# Pure_VCO.net
KiCad netlist of a schematic drawn in EAGLE
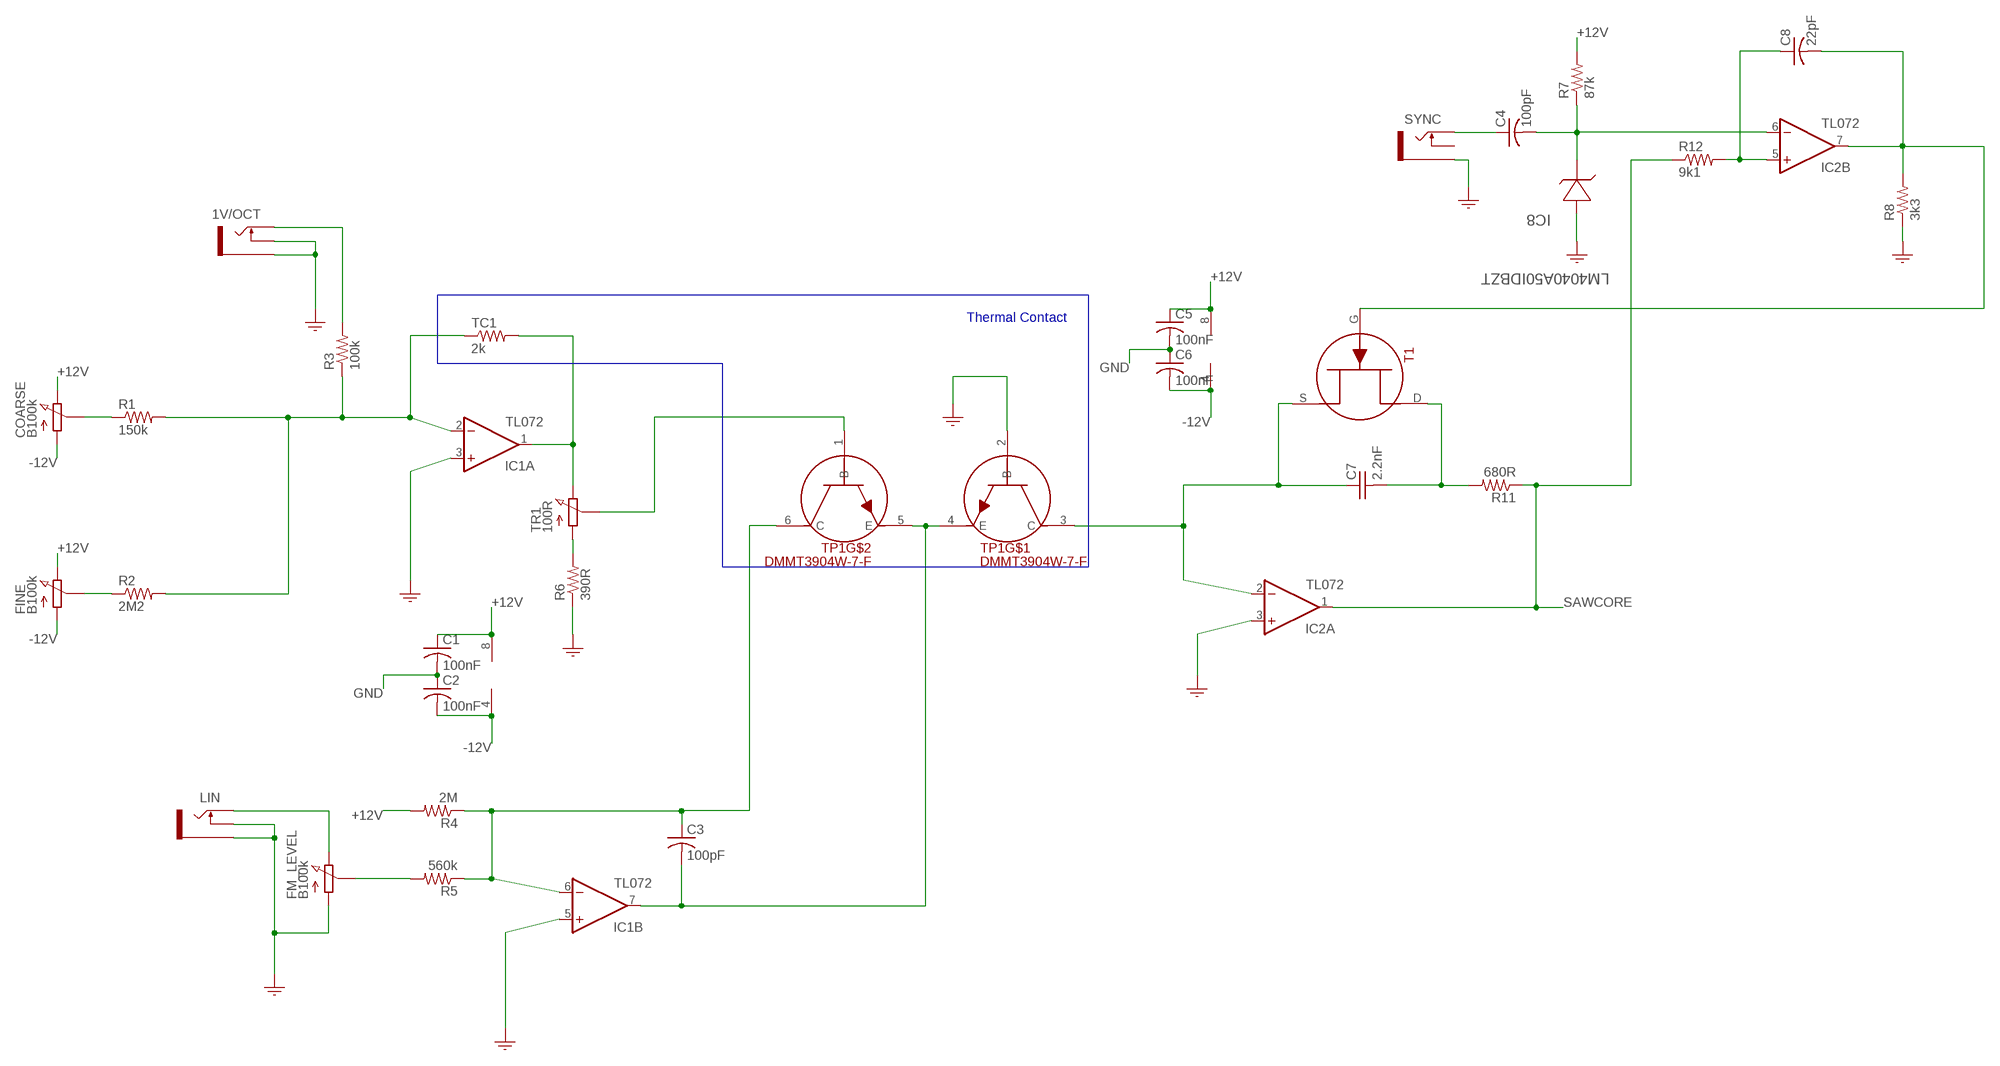
[diagram p0: schematic, sheet 1]
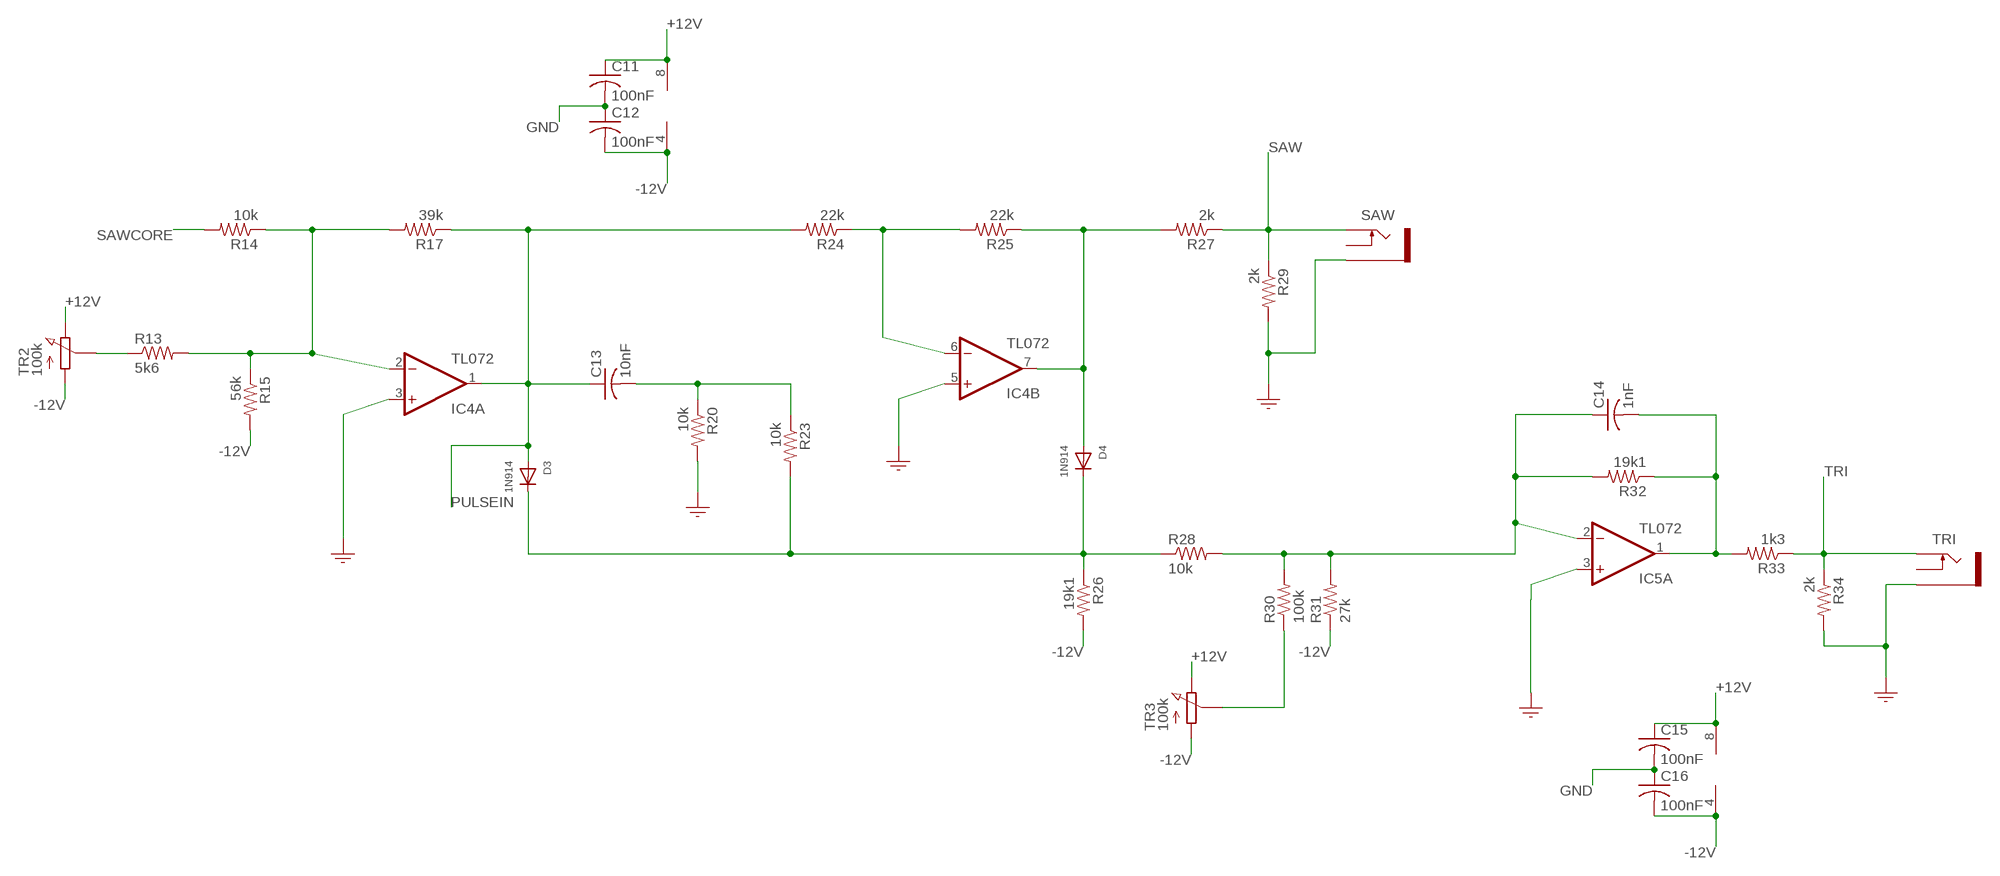
[diagram p1: schematic, sheet 2]
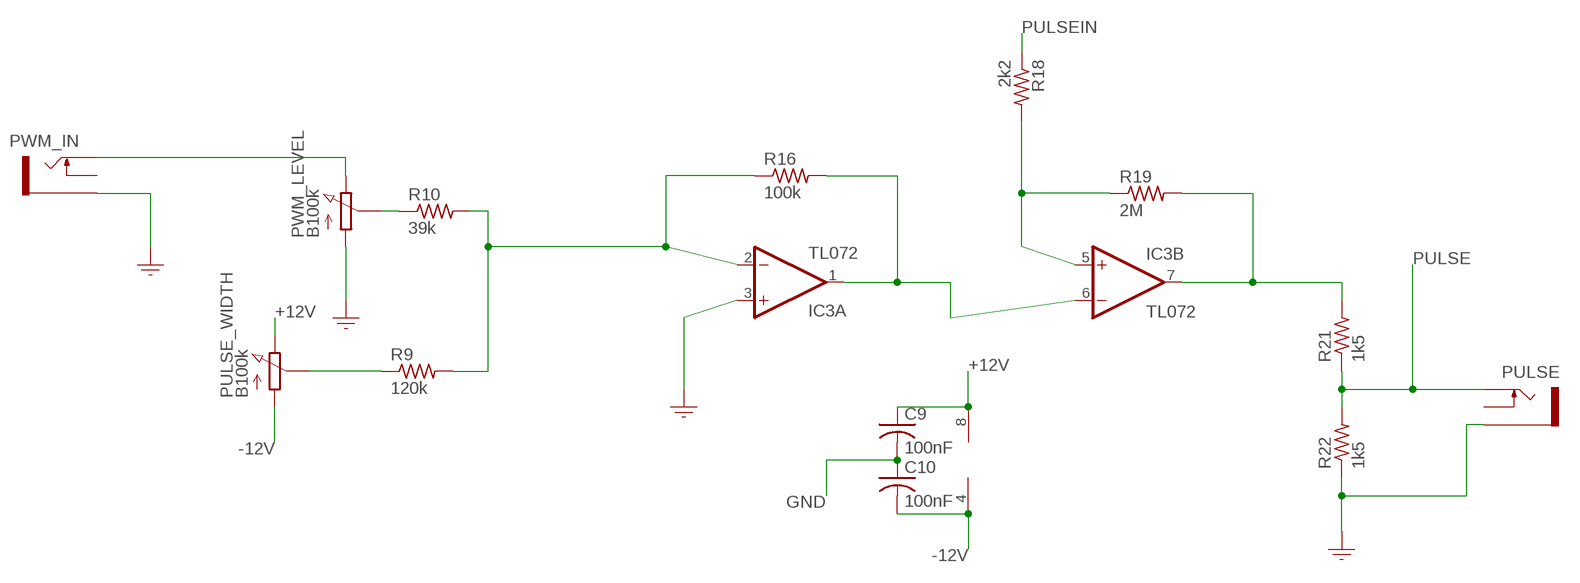
[diagram p2: schematic, sheet 3]
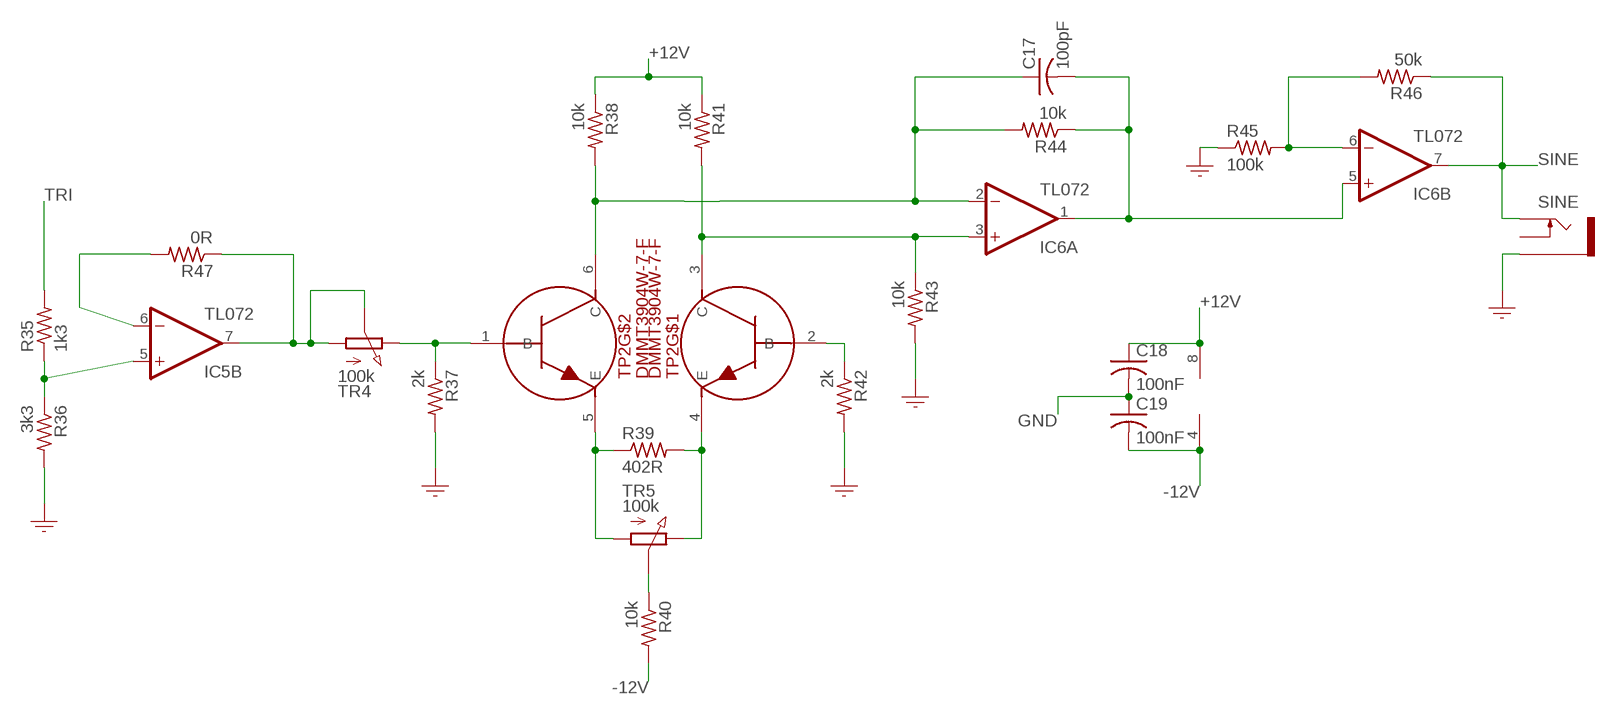
[diagram p3: schematic, sheet 4]
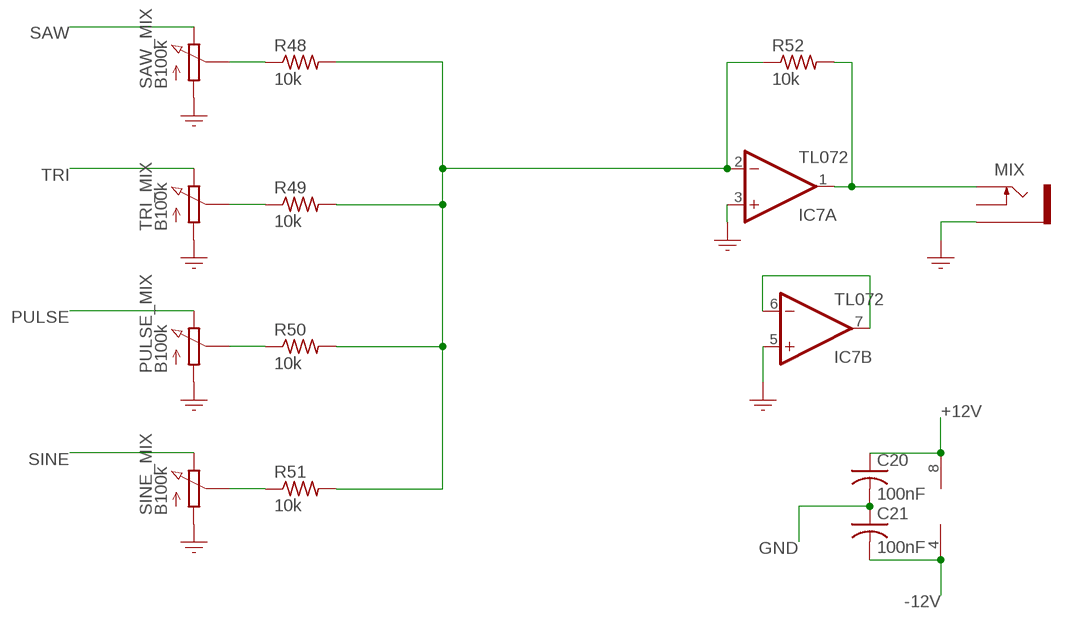
[diagram p4: schematic, sheet 5]
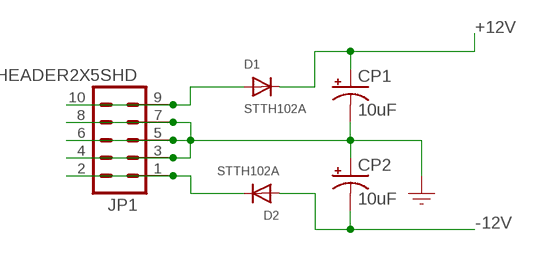
[diagram p5: schematic, sheet 6]

(export (version "E")
  (design (tool "Eeschema 10.0.6"))
  (components
    (comp (ref "C9")
      (value "100nF")
      (footprint "eagle-import:C0805")
      (libsource (lib "eagle-import") (part "CAPACITOR-USC0805"))
    )
    (comp (ref "C10")
      (value "100nF")
      (footprint "eagle-import:C0805")
      (libsource (lib "eagle-import") (part "CAPACITOR-USC0805"))
    )
    (comp (ref "IC3")
      (value "TL072")
      (footprint "eagle-import:SO08")
      (libsource (lib "eagle-import") (part "OPAMP_DUALD"))
    )
    (comp (ref "PULSE")
      (value "PJ301M-12")
      (footprint "eagle-import:PJ301M-12")
      (libsource (lib "eagle-import") (part "SOCKET_MONO_3.5MMPJ301M-12"))
    )
    (comp (ref "PULSE_WIDTH")
      (value "B100k")
      (footprint "eagle-import:POT_9MM_YELLOW_KNOB")
      (libsource (lib "eagle-import") (part "RESISTOR_VARIABLEPOT_9MM_YELLOW_KNOB"))
    )
    (comp (ref "PWM_IN")
      (value "PJ301M-12")
      (footprint "eagle-import:PJ301M-12")
      (libsource (lib "eagle-import") (part "SOCKET_MONO_3.5MMPJ301M-12"))
    )
    (comp (ref "PWM_LEVEL")
      (value "B100k")
      (footprint "eagle-import:POT_9MM_GREEN_KNOB")
      (libsource (lib "eagle-import") (part "RESISTOR_VARIABLEPOT_9MM_GREEN_KNOB"))
    )
    (comp (ref "R9")
      (value "120k")
      (footprint "eagle-import:R0805")
      (libsource (lib "eagle-import") (part "RESISTOR_USR0805"))
    )
    (comp (ref "R10")
      (value "39k")
      (footprint "eagle-import:R0805")
      (libsource (lib "eagle-import") (part "RESISTOR_USR0805"))
    )
    (comp (ref "R16")
      (value "100k")
      (footprint "eagle-import:R0805")
      (libsource (lib "eagle-import") (part "RESISTOR_USR0805"))
    )
    (comp (ref "R18")
      (value "2k2")
      (footprint "eagle-import:R0805")
      (libsource (lib "eagle-import") (part "RESISTOR_USR0805"))
    )
    (comp (ref "R19")
      (value "2M")
      (footprint "eagle-import:R0805")
      (libsource (lib "eagle-import") (part "RESISTOR_USR0805"))
    )
    (comp (ref "R21")
      (value "1k5")
      (footprint "eagle-import:R0805")
      (libsource (lib "eagle-import") (part "RESISTOR_USR0805"))
    )
    (comp (ref "R22")
      (value "1k5")
      (footprint "eagle-import:R0805")
      (libsource (lib "eagle-import") (part "RESISTOR_USR0805"))
    )
    (comp (ref "C11")
      (value "100nF")
      (footprint "eagle-import:C0805")
      (libsource (lib "eagle-import") (part "CAPACITOR-USC0805"))
    )
    (comp (ref "C12")
      (value "100nF")
      (footprint "eagle-import:C0805")
      (libsource (lib "eagle-import") (part "CAPACITOR-USC0805"))
    )
    (comp (ref "C13")
      (value "10nF")
      (footprint "eagle-import:C0805")
      (libsource (lib "eagle-import") (part "CAPACITOR-USC0805"))
    )
    (comp (ref "C14")
      (value "1nF")
      (footprint "eagle-import:C0805")
      (libsource (lib "eagle-import") (part "CAPACITOR-USC0805"))
    )
    (comp (ref "C15")
      (value "100nF")
      (footprint "eagle-import:C0805")
      (libsource (lib "eagle-import") (part "CAPACITOR-USC0805"))
    )
    (comp (ref "C16")
      (value "100nF")
      (footprint "eagle-import:C0805")
      (libsource (lib "eagle-import") (part "CAPACITOR-USC0805"))
    )
    (comp (ref "D3")
      (value "1N914")
      (footprint "eagle-import:SOD-323F")
      (libsource (lib "eagle-import") (part "DIODESOD-323F"))
    )
    (comp (ref "D4")
      (value "1N914")
      (footprint "eagle-import:SOD-323F")
      (libsource (lib "eagle-import") (part "DIODESOD-323F"))
    )
    (comp (ref "IC4")
      (value "TL072")
      (footprint "eagle-import:SO08")
      (libsource (lib "eagle-import") (part "OPAMP_DUALD"))
    )
    (comp (ref "IC5")
      (value "TL072")
      (footprint "eagle-import:SO08")
      (libsource (lib "eagle-import") (part "OPAMP_DUALD"))
    )
    (comp (ref "R13")
      (value "5k6")
      (footprint "eagle-import:R0805")
      (libsource (lib "eagle-import") (part "RESISTOR_USR0805"))
    )
    (comp (ref "R14")
      (value "10k")
      (footprint "eagle-import:R0805")
      (libsource (lib "eagle-import") (part "RESISTOR_USR0805"))
    )
    (comp (ref "R15")
      (value "56k")
      (footprint "eagle-import:R0805")
      (libsource (lib "eagle-import") (part "RESISTOR_USR0805"))
    )
    (comp (ref "R17")
      (value "39k")
      (footprint "eagle-import:R0805")
      (libsource (lib "eagle-import") (part "RESISTOR_USR0805"))
    )
    (comp (ref "R20")
      (value "10k")
      (footprint "eagle-import:R0805")
      (libsource (lib "eagle-import") (part "RESISTOR_USR0805"))
    )
    (comp (ref "R23")
      (value "10k")
      (footprint "eagle-import:R0805")
      (libsource (lib "eagle-import") (part "RESISTOR_USR0805"))
    )
    (comp (ref "R24")
      (value "22k")
      (footprint "eagle-import:R0805")
      (libsource (lib "eagle-import") (part "RESISTOR_USR0805"))
    )
    (comp (ref "R25")
      (value "22k")
      (footprint "eagle-import:R0805")
      (libsource (lib "eagle-import") (part "RESISTOR_USR0805"))
    )
    (comp (ref "R26")
      (value "19k1")
      (footprint "eagle-import:R0805")
      (libsource (lib "eagle-import") (part "RESISTOR_USR0805"))
    )
    (comp (ref "R27")
      (value "2k")
      (footprint "eagle-import:R0805")
      (libsource (lib "eagle-import") (part "RESISTOR_USR0805"))
    )
    (comp (ref "R28")
      (value "10k")
      (footprint "eagle-import:R0805")
      (libsource (lib "eagle-import") (part "RESISTOR_USR0805"))
    )
    (comp (ref "R29")
      (value "2k")
      (footprint "eagle-import:R0805")
      (libsource (lib "eagle-import") (part "RESISTOR_USR0805"))
    )
    (comp (ref "R30")
      (value "100k")
      (footprint "eagle-import:R0805")
      (libsource (lib "eagle-import") (part "RESISTOR_USR0805"))
    )
    (comp (ref "R31")
      (value "27k")
      (footprint "eagle-import:R0805")
      (libsource (lib "eagle-import") (part "RESISTOR_USR0805"))
    )
    (comp (ref "R32")
      (value "19k1")
      (footprint "eagle-import:R0805")
      (libsource (lib "eagle-import") (part "RESISTOR_USR0805"))
    )
    (comp (ref "R33")
      (value "1k3")
      (footprint "eagle-import:R0805")
      (libsource (lib "eagle-import") (part "RESISTOR_USR0805"))
    )
    (comp (ref "R34")
      (value "2k")
      (footprint "eagle-import:R0805")
      (libsource (lib "eagle-import") (part "RESISTOR_USR0805"))
    )
    (comp (ref "SAW")
      (value "PJ301M-12")
      (footprint "eagle-import:PJ301M-12")
      (libsource (lib "eagle-import") (part "SOCKET_MONO_3.5MMPJ301M-12"))
    )
    (comp (ref "TR2")
      (value "100k")
      (footprint "eagle-import:TRIMMER_TH")
      (libsource (lib "eagle-import") (part "RESISTOR_VARIABLETRIMMER_TH"))
    )
    (comp (ref "TR3")
      (value "100k")
      (footprint "eagle-import:TRIMMER_TH")
      (libsource (lib "eagle-import") (part "RESISTOR_VARIABLETRIMMER_TH"))
    )
    (comp (ref "TRI")
      (value "PJ301M-12")
      (footprint "eagle-import:PJ301M-12")
      (libsource (lib "eagle-import") (part "SOCKET_MONO_3.5MMPJ301M-12"))
    )
    (comp (ref "CP1")
      (value "10uF")
      (footprint "eagle-import:153CLV-0505")
      (libsource (lib "eagle-import") (part "CAPACITOR_POL-US153CLV-0505"))
    )
    (comp (ref "CP2")
      (value "10uF")
      (footprint "eagle-import:153CLV-0505")
      (libsource (lib "eagle-import") (part "CAPACITOR_POL-US153CLV-0505"))
    )
    (comp (ref "D1")
      (value "STTH102A")
      (footprint "eagle-import:SMADIODE")
      (libsource (lib "eagle-import") (part "DIODESMA"))
    )
    (comp (ref "D2")
      (value "STTH102A")
      (footprint "eagle-import:SMADIODE")
      (libsource (lib "eagle-import") (part "DIODESMA"))
    )
    (comp (ref "JP1")
      (value "HEADER2X5SHD")
      (footprint "eagle-import:2X5-SHROUDED")
      (libsource (lib "eagle-import") (part "HEADER2X5SHD"))
    )
    (comp (ref "C17")
      (value "100pF")
      (footprint "eagle-import:C0805")
      (libsource (lib "eagle-import") (part "CAPACITOR-USC0805"))
    )
    (comp (ref "C18")
      (value "100nF")
      (footprint "eagle-import:C0805")
      (libsource (lib "eagle-import") (part "CAPACITOR-USC0805"))
    )
    (comp (ref "C19")
      (value "100nF")
      (footprint "eagle-import:C0805")
      (libsource (lib "eagle-import") (part "CAPACITOR-USC0805"))
    )
    (comp (ref "IC6")
      (value "TL072")
      (footprint "eagle-import:SO08")
      (libsource (lib "eagle-import") (part "OPAMP_DUALD"))
    )
    (comp (ref "R35")
      (value "1k3")
      (footprint "eagle-import:R0805")
      (libsource (lib "eagle-import") (part "RESISTOR_USR0805"))
    )
    (comp (ref "R36")
      (value "3k3")
      (footprint "eagle-import:R0805")
      (libsource (lib "eagle-import") (part "RESISTOR_USR0805"))
    )
    (comp (ref "R37")
      (value "2k")
      (footprint "eagle-import:R0805")
      (libsource (lib "eagle-import") (part "RESISTOR_USR0805"))
    )
    (comp (ref "R38")
      (value "10k")
      (footprint "eagle-import:R0805")
      (libsource (lib "eagle-import") (part "RESISTOR_USR0805"))
    )
    (comp (ref "R39")
      (value "402R")
      (footprint "eagle-import:R0805")
      (libsource (lib "eagle-import") (part "RESISTOR_USR0805"))
    )
    (comp (ref "R40")
      (value "10k")
      (footprint "eagle-import:R0805")
      (libsource (lib "eagle-import") (part "RESISTOR_USR0805"))
    )
    (comp (ref "R41")
      (value "10k")
      (footprint "eagle-import:R0805")
      (libsource (lib "eagle-import") (part "RESISTOR_USR0805"))
    )
    (comp (ref "R42")
      (value "2k")
      (footprint "eagle-import:R0805")
      (libsource (lib "eagle-import") (part "RESISTOR_USR0805"))
    )
    (comp (ref "R43")
      (value "10k")
      (footprint "eagle-import:R0805")
      (libsource (lib "eagle-import") (part "RESISTOR_USR0805"))
    )
    (comp (ref "R44")
      (value "10k")
      (footprint "eagle-import:R0805")
      (libsource (lib "eagle-import") (part "RESISTOR_USR0805"))
    )
    (comp (ref "R45")
      (value "100k")
      (footprint "eagle-import:R0805")
      (libsource (lib "eagle-import") (part "RESISTOR_USR0805"))
    )
    (comp (ref "R46")
      (value "50k")
      (footprint "eagle-import:R0805")
      (libsource (lib "eagle-import") (part "RESISTOR_USR0805"))
    )
    (comp (ref "R47")
      (value "0R")
      (footprint "eagle-import:R0805")
      (libsource (lib "eagle-import") (part "RESISTOR_USR0805"))
    )
    (comp (ref "SINE")
      (value "PJ301M-12")
      (footprint "eagle-import:PJ301M-12")
      (libsource (lib "eagle-import") (part "SOCKET_MONO_3.5MMPJ301M-12"))
    )
    (comp (ref "TP2")
      (value "DMMT3904W-7-F")
      (footprint "eagle-import:TRANS_PAIR")
      (libsource (lib "eagle-import") (part "TRANSISTOR_PAIR_NPN"))
    )
    (comp (ref "TR4")
      (value "100k")
      (footprint "eagle-import:TRIMMER_TH")
      (libsource (lib "eagle-import") (part "RESISTOR_VARIABLETRIMMER_TH"))
    )
    (comp (ref "TR5")
      (value "100k")
      (footprint "eagle-import:TRIMMER_TH")
      (libsource (lib "eagle-import") (part "RESISTOR_VARIABLETRIMMER_TH"))
    )
    (comp (ref "C20")
      (value "100nF")
      (footprint "eagle-import:C0805")
      (libsource (lib "eagle-import") (part "CAPACITOR-USC0805"))
    )
    (comp (ref "C21")
      (value "100nF")
      (footprint "eagle-import:C0805")
      (libsource (lib "eagle-import") (part "CAPACITOR-USC0805"))
    )
    (comp (ref "IC7")
      (value "TL072")
      (footprint "eagle-import:SO08")
      (libsource (lib "eagle-import") (part "OPAMP_DUALD"))
    )
    (comp (ref "MIX")
      (value "PJ301M-12")
      (footprint "eagle-import:PJ301M-12")
      (libsource (lib "eagle-import") (part "SOCKET_MONO_3.5MMPJ301M-12"))
    )
    (comp (ref "PULSE_MIX")
      (value "B100k")
      (footprint "eagle-import:POT_9MM_BLUE_KNOB")
      (libsource (lib "eagle-import") (part "RESISTOR_VARIABLEPOT_9MM_BLUE_KNOB"))
    )
    (comp (ref "R48")
      (value "10k")
      (footprint "eagle-import:R0805")
      (libsource (lib "eagle-import") (part "RESISTOR_USR0805"))
    )
    (comp (ref "R49")
      (value "10k")
      (footprint "eagle-import:R0805")
      (libsource (lib "eagle-import") (part "RESISTOR_USR0805"))
    )
    (comp (ref "R50")
      (value "10k")
      (footprint "eagle-import:R0805")
      (libsource (lib "eagle-import") (part "RESISTOR_USR0805"))
    )
    (comp (ref "R51")
      (value "10k")
      (footprint "eagle-import:R0805")
      (libsource (lib "eagle-import") (part "RESISTOR_USR0805"))
    )
    (comp (ref "R52")
      (value "10k")
      (footprint "eagle-import:R0805")
      (libsource (lib "eagle-import") (part "RESISTOR_USR0805"))
    )
    (comp (ref "SAW_MIX")
      (value "B100k")
      (footprint "eagle-import:POT_9MM_BLUE_KNOB")
      (libsource (lib "eagle-import") (part "RESISTOR_VARIABLEPOT_9MM_BLUE_KNOB"))
    )
    (comp (ref "SINE_MIX")
      (value "B100k")
      (footprint "eagle-import:POT_9MM_BLUE_KNOB")
      (libsource (lib "eagle-import") (part "RESISTOR_VARIABLEPOT_9MM_BLUE_KNOB"))
    )
    (comp (ref "TRI_MIX")
      (value "B100k")
      (footprint "eagle-import:POT_9MM_BLUE_KNOB")
      (libsource (lib "eagle-import") (part "RESISTOR_VARIABLEPOT_9MM_BLUE_KNOB"))
    )
    (comp (ref "1V/OCT")
      (value "PJ301M-12")
      (footprint "eagle-import:PJ301M-12")
      (libsource (lib "eagle-import") (part "SOCKET_MONO_3.5MMPJ301M-12"))
    )
    (comp (ref "C1")
      (value "100nF")
      (footprint "eagle-import:C0805")
      (libsource (lib "eagle-import") (part "CAPACITOR-USC0805"))
    )
    (comp (ref "C2")
      (value "100nF")
      (footprint "eagle-import:C0805")
      (libsource (lib "eagle-import") (part "CAPACITOR-USC0805"))
    )
    (comp (ref "C3")
      (value "100pF")
      (footprint "eagle-import:C0805")
      (libsource (lib "eagle-import") (part "CAPACITOR-USC0805"))
    )
    (comp (ref "C4")
      (value "100pF")
      (footprint "eagle-import:C0805")
      (libsource (lib "eagle-import") (part "CAPACITOR-USC0805"))
    )
    (comp (ref "C5")
      (value "100nF")
      (footprint "eagle-import:C0805")
      (libsource (lib "eagle-import") (part "CAPACITOR-USC0805"))
    )
    (comp (ref "C6")
      (value "100nF")
      (footprint "eagle-import:C0805")
      (libsource (lib "eagle-import") (part "CAPACITOR-USC0805"))
    )
    (comp (ref "C7")
      (value "2.2nF")
      (footprint "eagle-import:POLY_CAP")
      (libsource (lib "eagle-import") (part "CAPACITOR_POLYFILM"))
    )
    (comp (ref "C8")
      (value "22pF")
      (footprint "eagle-import:C0805")
      (libsource (lib "eagle-import") (part "CAPACITOR-USC0805"))
    )
    (comp (ref "COARSE")
      (value "B100k")
      (footprint "eagle-import:POT_9MM_RED_KNOB")
      (libsource (lib "eagle-import") (part "RESISTOR_VARIABLEPOT_9MM_RED_KNOB"))
    )
    (comp (ref "FINE")
      (value "B100k")
      (footprint "eagle-import:POT_9MM_RED_MXR_KNOB")
      (libsource (lib "eagle-import") (part "RESISTOR_VARIABLEPOT_9MM_RED_MXR_KNOB"))
    )
    (comp (ref "FM_LEVEL")
      (value "B100k")
      (footprint "eagle-import:POT_9MM_GREEN_KNOB")
      (libsource (lib "eagle-import") (part "RESISTOR_VARIABLEPOT_9MM_GREEN_KNOB"))
    )
    (comp (ref "IC1")
      (value "TL072")
      (footprint "eagle-import:SO08")
      (libsource (lib "eagle-import") (part "OPAMP_DUALD"))
    )
    (comp (ref "IC2")
      (value "TL072")
      (footprint "eagle-import:SO08")
      (libsource (lib "eagle-import") (part "OPAMP_DUALD"))
    )
    (comp (ref "IC8")
      (value "LM4040A50IDBZT")
      (footprint "eagle-import:SOT95P237X112-3N")
      (libsource (lib "eagle-import") (part "VOLTAGE_REF"))
    )
    (comp (ref "LIN")
      (value "PJ301M-12")
      (footprint "eagle-import:PJ301M-12")
      (libsource (lib "eagle-import") (part "SOCKET_MONO_3.5MMPJ301M-12"))
    )
    (comp (ref "R1")
      (value "150k")
      (footprint "eagle-import:R0805")
      (libsource (lib "eagle-import") (part "RESISTOR_USR0805"))
    )
    (comp (ref "R2")
      (value "2M2")
      (footprint "eagle-import:R0805")
      (libsource (lib "eagle-import") (part "RESISTOR_USR0805"))
    )
    (comp (ref "R3")
      (value "100k")
      (footprint "eagle-import:R0805")
      (libsource (lib "eagle-import") (part "RESISTOR_USR0805"))
    )
    (comp (ref "R4")
      (value "2M")
      (footprint "eagle-import:R0805")
      (libsource (lib "eagle-import") (part "RESISTOR_USR0805"))
    )
    (comp (ref "R5")
      (value "560k")
      (footprint "eagle-import:R0805")
      (libsource (lib "eagle-import") (part "RESISTOR_USR0805"))
    )
    (comp (ref "R6")
      (value "390R")
      (footprint "eagle-import:R0805")
      (libsource (lib "eagle-import") (part "RESISTOR_USR0805"))
    )
    (comp (ref "R7")
      (value "87k")
      (footprint "eagle-import:R0805")
      (libsource (lib "eagle-import") (part "RESISTOR_USR0805"))
    )
    (comp (ref "R8")
      (value "3k3")
      (footprint "eagle-import:R0805")
      (libsource (lib "eagle-import") (part "RESISTOR_USR0805"))
    )
    (comp (ref "R11")
      (value "680R")
      (footprint "eagle-import:R0805")
      (libsource (lib "eagle-import") (part "RESISTOR_USR0805"))
    )
    (comp (ref "R12")
      (value "9k1")
      (footprint "eagle-import:R0805")
      (libsource (lib "eagle-import") (part "RESISTOR_USR0805"))
    )
    (comp (ref "SYNC")
      (value "PJ301M-12")
      (footprint "eagle-import:PJ301M-12")
      (libsource (lib "eagle-import") (part "SOCKET_MONO_3.5MMPJ301M-12"))
    )
    (comp (ref "T1")
      (value "MMBFJ309")
      (footprint "eagle-import:N_CHN")
      (libsource (lib "eagle-import") (part "TRANSISTOR_JFET_N_CHN"))
    )
    (comp (ref "TC1")
      (value "2k")
      (footprint "eagle-import:0207_8.5")
      (libsource (lib "eagle-import") (part "RESISTOR_US0207/8.5"))
    )
    (comp (ref "TP1")
      (value "DMMT3904W-7-F")
      (footprint "eagle-import:TRANS_PAIR")
      (libsource (lib "eagle-import") (part "TRANSISTOR_PAIR_NPN"))
    )
    (comp (ref "TR1")
      (value "100R")
      (footprint "eagle-import:TRIMMER_TH")
      (libsource (lib "eagle-import") (part "RESISTOR_VARIABLETRIMMER_TH"))
    )
  )
  (nets
    (net (code "1") (name "+12V") (class "Default")
      (node (ref "C1") (pin "1") (pinfunction "1_1") (pintype "passive"))
      (node (ref "C11") (pin "1") (pinfunction "1_1") (pintype "passive"))
      (node (ref "C15") (pin "1") (pinfunction "1_1") (pintype "passive"))
      (node (ref "C18") (pin "1") (pinfunction "1_1") (pintype "passive"))
      (node (ref "C20") (pin "1") (pinfunction "1_1") (pintype "passive"))
      (node (ref "C5") (pin "1") (pinfunction "1_1") (pintype "passive"))
      (node (ref "C9") (pin "1") (pinfunction "1_1") (pintype "passive"))
      (node (ref "COARSE") (pin "P$3") (pinfunction "3_P$3") (pintype "passive"))
      (node (ref "CP1") (pin "+") (pinfunction "+_+") (pintype "passive"))
      (node (ref "D1") (pin "C") (pinfunction "C_C") (pintype "passive"))
      (node (ref "FINE") (pin "P$3") (pinfunction "3_P$3") (pintype "passive"))
      (node (ref "IC1") (pin "8") (pinfunction "V+_8") (pintype "power_in"))
      (node (ref "IC2") (pin "8") (pinfunction "V+_8") (pintype "power_in"))
      (node (ref "IC3") (pin "8") (pinfunction "V+_8") (pintype "power_in"))
      (node (ref "IC4") (pin "8") (pinfunction "V+_8") (pintype "power_in"))
      (node (ref "IC5") (pin "8") (pinfunction "V+_8") (pintype "power_in"))
      (node (ref "IC6") (pin "8") (pinfunction "V+_8") (pintype "power_in"))
      (node (ref "IC7") (pin "8") (pinfunction "V+_8") (pintype "power_in"))
      (node (ref "PULSE_WIDTH") (pin "P$3") (pinfunction "3_P$3") (pintype "passive"))
      (node (ref "R38") (pin "1") (pinfunction "1_1") (pintype "passive"))
      (node (ref "R4") (pin "2") (pinfunction "2_2") (pintype "passive"))
      (node (ref "R41") (pin "1") (pinfunction "1_1") (pintype "passive"))
      (node (ref "R7") (pin "2") (pinfunction "2_2") (pintype "passive"))
      (node (ref "TR2") (pin "3") (pinfunction "3_3") (pintype "passive"))
      (node (ref "TR3") (pin "3") (pinfunction "3_3") (pintype "passive"))
    )
    (net (code "2") (name "-12V") (class "Default")
      (node (ref "C10") (pin "2") (pinfunction "2_2") (pintype "passive"))
      (node (ref "C12") (pin "2") (pinfunction "2_2") (pintype "passive"))
      (node (ref "C16") (pin "2") (pinfunction "2_2") (pintype "passive"))
      (node (ref "C19") (pin "2") (pinfunction "2_2") (pintype "passive"))
      (node (ref "C2") (pin "2") (pinfunction "2_2") (pintype "passive"))
      (node (ref "C21") (pin "2") (pinfunction "2_2") (pintype "passive"))
      (node (ref "C6") (pin "2") (pinfunction "2_2") (pintype "passive"))
      (node (ref "COARSE") (pin "P$1") (pinfunction "1_P$1") (pintype "passive"))
      (node (ref "CP2") (pin "-") (pinfunction "-_-") (pintype "passive"))
      (node (ref "D2") (pin "A") (pinfunction "A_A") (pintype "passive"))
      (node (ref "FINE") (pin "P$1") (pinfunction "1_P$1") (pintype "passive"))
      (node (ref "IC1") (pin "4") (pinfunction "V-_4") (pintype "power_in"))
      (node (ref "IC2") (pin "4") (pinfunction "V-_4") (pintype "power_in"))
      (node (ref "IC3") (pin "4") (pinfunction "V-_4") (pintype "power_in"))
      (node (ref "IC4") (pin "4") (pinfunction "V-_4") (pintype "power_in"))
      (node (ref "IC5") (pin "4") (pinfunction "V-_4") (pintype "power_in"))
      (node (ref "IC6") (pin "4") (pinfunction "V-_4") (pintype "power_in"))
      (node (ref "IC7") (pin "4") (pinfunction "V-_4") (pintype "power_in"))
      (node (ref "PULSE_WIDTH") (pin "P$1") (pinfunction "1_P$1") (pintype "passive"))
      (node (ref "R15") (pin "2") (pinfunction "2_2") (pintype "passive"))
      (node (ref "R26") (pin "2") (pinfunction "2_2") (pintype "passive"))
      (node (ref "R31") (pin "1") (pinfunction "1_1") (pintype "passive"))
      (node (ref "R40") (pin "2") (pinfunction "2_2") (pintype "passive"))
      (node (ref "TR2") (pin "1") (pinfunction "1_1") (pintype "passive"))
      (node (ref "TR3") (pin "1") (pinfunction "1_1") (pintype "passive"))
    )
    (net (code "3") (name "GND") (class "Default")
      (node (ref "1V/OCT") (pin "GND") (pinfunction "SLEEVE_GND") (pintype "passive"))
      (node (ref "1V/OCT") (pin "NORM") (pinfunction "SWITCH_NORM") (pintype "passive"))
      (node (ref "C1") (pin "2") (pinfunction "2_2") (pintype "passive"))
      (node (ref "C10") (pin "1") (pinfunction "1_1") (pintype "passive"))
      (node (ref "C11") (pin "2") (pinfunction "2_2") (pintype "passive"))
      (node (ref "C12") (pin "1") (pinfunction "1_1") (pintype "passive"))
      (node (ref "C15") (pin "2") (pinfunction "2_2") (pintype "passive"))
      (node (ref "C16") (pin "1") (pinfunction "1_1") (pintype "passive"))
      (node (ref "C18") (pin "2") (pinfunction "2_2") (pintype "passive"))
      (node (ref "C19") (pin "1") (pinfunction "1_1") (pintype "passive"))
      (node (ref "C2") (pin "1") (pinfunction "1_1") (pintype "passive"))
      (node (ref "C20") (pin "2") (pinfunction "2_2") (pintype "passive"))
      (node (ref "C21") (pin "1") (pinfunction "1_1") (pintype "passive"))
      (node (ref "C5") (pin "2") (pinfunction "2_2") (pintype "passive"))
      (node (ref "C6") (pin "1") (pinfunction "1_1") (pintype "passive"))
      (node (ref "C9") (pin "2") (pinfunction "2_2") (pintype "passive"))
      (node (ref "CP1") (pin "-") (pinfunction "-_-") (pintype "passive"))
      (node (ref "CP2") (pin "+") (pinfunction "+_+") (pintype "passive"))
      (node (ref "FM_LEVEL") (pin "P$1") (pinfunction "1_P$1") (pintype "passive"))
      (node (ref "IC1") (pin "3") (pinfunction "+IN_3") (pintype "input"))
      (node (ref "IC1") (pin "5") (pinfunction "+IN_5") (pintype "input"))
      (node (ref "IC2") (pin "3") (pinfunction "+IN_3") (pintype "input"))
      (node (ref "IC3") (pin "3") (pinfunction "+IN_3") (pintype "input"))
      (node (ref "IC4") (pin "3") (pinfunction "+IN_3") (pintype "input"))
      (node (ref "IC4") (pin "5") (pinfunction "+IN_5") (pintype "input"))
      (node (ref "IC5") (pin "3") (pinfunction "+IN_3") (pintype "input"))
      (node (ref "IC7") (pin "3") (pinfunction "+IN_3") (pintype "input"))
      (node (ref "IC7") (pin "5") (pinfunction "+IN_5") (pintype "input"))
      (node (ref "IC8") (pin "2") (pinfunction "ANODE_2") (pintype "input"))
      (node (ref "JP1") (pin "3") (pinfunction "3_3") (pintype "passive"))
      (node (ref "JP1") (pin "4") (pinfunction "4_4") (pintype "passive"))
      (node (ref "JP1") (pin "5") (pinfunction "5_5") (pintype "passive"))
      (node (ref "JP1") (pin "6") (pinfunction "6_6") (pintype "passive"))
      (node (ref "JP1") (pin "7") (pinfunction "7_7") (pintype "passive"))
      (node (ref "JP1") (pin "8") (pinfunction "8_8") (pintype "passive"))
      (node (ref "LIN") (pin "GND") (pinfunction "SLEEVE_GND") (pintype "passive"))
      (node (ref "LIN") (pin "NORM") (pinfunction "SWITCH_NORM") (pintype "passive"))
      (node (ref "MIX") (pin "GND") (pinfunction "SLEEVE_GND") (pintype "passive"))
      (node (ref "PULSE") (pin "GND") (pinfunction "SLEEVE_GND") (pintype "passive"))
      (node (ref "PULSE_MIX") (pin "P$1") (pinfunction "1_P$1") (pintype "passive"))
      (node (ref "PWM_IN") (pin "GND") (pinfunction "SLEEVE_GND") (pintype "passive"))
      (node (ref "PWM_LEVEL") (pin "P$1") (pinfunction "1_P$1") (pintype "passive"))
      (node (ref "R20") (pin "2") (pinfunction "2_2") (pintype "passive"))
      (node (ref "R22") (pin "1") (pinfunction "1_1") (pintype "passive"))
      (node (ref "R29") (pin "2") (pinfunction "2_2") (pintype "passive"))
      (node (ref "R34") (pin "2") (pinfunction "2_2") (pintype "passive"))
      (node (ref "R36") (pin "2") (pinfunction "2_2") (pintype "passive"))
      (node (ref "R37") (pin "2") (pinfunction "2_2") (pintype "passive"))
      (node (ref "R42") (pin "2") (pinfunction "2_2") (pintype "passive"))
      (node (ref "R43") (pin "2") (pinfunction "2_2") (pintype "passive"))
      (node (ref "R45") (pin "1") (pinfunction "1_1") (pintype "passive"))
      (node (ref "R6") (pin "1") (pinfunction "1_1") (pintype "passive"))
      (node (ref "R8") (pin "1") (pinfunction "1_1") (pintype "passive"))
      (node (ref "SAW") (pin "GND") (pinfunction "SLEEVE_GND") (pintype "passive"))
      (node (ref "SAW_MIX") (pin "P$1") (pinfunction "1_P$1") (pintype "passive"))
      (node (ref "SINE") (pin "GND") (pinfunction "SLEEVE_GND") (pintype "passive"))
      (node (ref "SINE_MIX") (pin "P$1") (pinfunction "1_P$1") (pintype "passive"))
      (node (ref "SYNC") (pin "GND") (pinfunction "SLEEVE_GND") (pintype "passive"))
      (node (ref "TP1") (pin "2") (pinfunction "B_2") (pintype "bidirectional"))
      (node (ref "TRI") (pin "GND") (pinfunction "SLEEVE_GND") (pintype "passive"))
      (node (ref "TRI_MIX") (pin "P$1") (pinfunction "1_P$1") (pintype "passive"))
    )
    (net (code "4") (name "Net-(1V/OCT-PadTIP)") (class "Default")
      (node (ref "1V/OCT") (pin "TIP") (pinfunction "TIP_TIP") (pintype "passive"))
      (node (ref "R3") (pin "2") (pinfunction "2_2") (pintype "passive"))
    )
    (net (code "5") (name "Net-(C4-Pad1)") (class "Default")
      (node (ref "C4") (pin "1") (pinfunction "1_1") (pintype "passive"))
      (node (ref "SYNC") (pin "TIP") (pinfunction "TIP_TIP") (pintype "passive"))
    )
    (net (code "6") (name "Net-(C7-+)") (class "Default")
      (node (ref "C7") (pin "1") (pinfunction "+_1") (pintype "passive"))
      (node (ref "IC2") (pin "2") (pinfunction "-IN_2") (pintype "input"))
      (node (ref "T1") (pin "S") (pinfunction "S_S") (pintype "bidirectional"))
      (node (ref "TP1") (pin "3") (pinfunction "C_3") (pintype "bidirectional"))
    )
    (net (code "7") (name "Net-(C7--)") (class "Default")
      (node (ref "C7") (pin "2") (pinfunction "-_2") (pintype "passive"))
      (node (ref "R11") (pin "2") (pinfunction "2_2") (pintype "passive"))
      (node (ref "T1") (pin "D") (pinfunction "D_D") (pintype "bidirectional"))
    )
    (net (code "8") (name "Net-(C13-Pad2)") (class "Default")
      (node (ref "C13") (pin "2") (pinfunction "2_2") (pintype "passive"))
      (node (ref "R20") (pin "1") (pinfunction "1_1") (pintype "passive"))
      (node (ref "R23") (pin "1") (pinfunction "1_1") (pintype "passive"))
    )
    (net (code "9") (name "Net-(COARSE-2)") (class "Default")
      (node (ref "COARSE") (pin "P$2") (pinfunction "2_P$2") (pintype "passive"))
      (node (ref "R1") (pin "1") (pinfunction "1_1") (pintype "passive"))
    )
    (net (code "10") (name "Net-(D1-PadA)") (class "Default")
      (node (ref "D1") (pin "A") (pinfunction "A_A") (pintype "passive"))
      (node (ref "JP1") (pin "10") (pinfunction "10_10") (pintype "passive"))
      (node (ref "JP1") (pin "9") (pinfunction "9_9") (pintype "passive"))
    )
    (net (code "11") (name "Net-(D2-PadC)") (class "Default")
      (node (ref "D2") (pin "C") (pinfunction "C_C") (pintype "passive"))
      (node (ref "JP1") (pin "1") (pinfunction "1_1") (pintype "passive"))
      (node (ref "JP1") (pin "2") (pinfunction "2_2") (pintype "passive"))
    )
    (net (code "12") (name "Net-(D3-PadC)") (class "Default")
      (node (ref "D3") (pin "C") (pinfunction "C_C") (pintype "passive"))
      (node (ref "D4") (pin "C") (pinfunction "C_C") (pintype "passive"))
      (node (ref "R23") (pin "2") (pinfunction "2_2") (pintype "passive"))
      (node (ref "R26") (pin "1") (pinfunction "1_1") (pintype "passive"))
      (node (ref "R28") (pin "1") (pinfunction "1_1") (pintype "passive"))
    )
    (net (code "13") (name "Net-(FINE-2)") (class "Default")
      (node (ref "FINE") (pin "P$2") (pinfunction "2_P$2") (pintype "passive"))
      (node (ref "R2") (pin "1") (pinfunction "1_1") (pintype "passive"))
    )
    (net (code "14") (name "Net-(FM_LEVEL-2)") (class "Default")
      (node (ref "FM_LEVEL") (pin "P$2") (pinfunction "2_P$2") (pintype "passive"))
      (node (ref "R5") (pin "2") (pinfunction "2_2") (pintype "passive"))
    )
    (net (code "15") (name "Net-(FM_LEVEL-3)") (class "Default")
      (node (ref "FM_LEVEL") (pin "P$3") (pinfunction "3_P$3") (pintype "passive"))
      (node (ref "LIN") (pin "TIP") (pinfunction "TIP_TIP") (pintype "passive"))
    )
    (net (code "16") (name "Net-(IC1A--IN)") (class "Default")
      (node (ref "IC1") (pin "2") (pinfunction "-IN_2") (pintype "input"))
      (node (ref "R1") (pin "2") (pinfunction "2_2") (pintype "passive"))
      (node (ref "R2") (pin "2") (pinfunction "2_2") (pintype "passive"))
      (node (ref "R3") (pin "1") (pinfunction "1_1") (pintype "passive"))
      (node (ref "TC1") (pin "1") (pinfunction "1_1") (pintype "passive"))
    )
    (net (code "17") (name "Net-(IC1A-OUT)") (class "Default")
      (node (ref "IC1") (pin "1") (pinfunction "OUT_1") (pintype "output"))
      (node (ref "TC1") (pin "2") (pinfunction "2_2") (pintype "passive"))
      (node (ref "TR1") (pin "3") (pinfunction "3_3") (pintype "passive"))
    )
    (net (code "18") (name "Net-(IC1B--IN)") (class "Default")
      (node (ref "C3") (pin "1") (pinfunction "1_1") (pintype "passive"))
      (node (ref "IC1") (pin "6") (pinfunction "-IN_6") (pintype "input"))
      (node (ref "R4") (pin "1") (pinfunction "1_1") (pintype "passive"))
      (node (ref "R5") (pin "1") (pinfunction "1_1") (pintype "passive"))
      (node (ref "TP1") (pin "6") (pinfunction "C_6") (pintype "bidirectional"))
    )
    (net (code "19") (name "Net-(IC1B-OUT)") (class "Default")
      (node (ref "C3") (pin "2") (pinfunction "2_2") (pintype "passive"))
      (node (ref "IC1") (pin "7") (pinfunction "OUT_7") (pintype "output"))
      (node (ref "TP1") (pin "4") (pinfunction "E_4") (pintype "bidirectional"))
      (node (ref "TP1") (pin "5") (pinfunction "E_5") (pintype "bidirectional"))
    )
    (net (code "20") (name "Net-(IC2B-+IN)") (class "Default")
      (node (ref "C8") (pin "1") (pinfunction "1_1") (pintype "passive"))
      (node (ref "IC2") (pin "5") (pinfunction "+IN_5") (pintype "input"))
      (node (ref "R12") (pin "2") (pinfunction "2_2") (pintype "passive"))
    )
    (net (code "21") (name "Net-(IC2B--IN)") (class "Default")
      (node (ref "C4") (pin "2") (pinfunction "2_2") (pintype "passive"))
      (node (ref "IC2") (pin "6") (pinfunction "-IN_6") (pintype "input"))
      (node (ref "IC8") (pin "1") (pinfunction "CATHODE_1") (pintype "output"))
      (node (ref "R7") (pin "1") (pinfunction "1_1") (pintype "passive"))
    )
    (net (code "22") (name "Net-(IC2B-OUT)") (class "Default")
      (node (ref "C8") (pin "2") (pinfunction "2_2") (pintype "passive"))
      (node (ref "IC2") (pin "7") (pinfunction "OUT_7") (pintype "output"))
      (node (ref "R8") (pin "2") (pinfunction "2_2") (pintype "passive"))
      (node (ref "T1") (pin "G") (pinfunction "G_G") (pintype "bidirectional"))
    )
    (net (code "23") (name "Net-(IC3A--IN)") (class "Default")
      (node (ref "IC3") (pin "2") (pinfunction "-IN_2") (pintype "input"))
      (node (ref "R10") (pin "2") (pinfunction "2_2") (pintype "passive"))
      (node (ref "R16") (pin "1") (pinfunction "1_1") (pintype "passive"))
      (node (ref "R9") (pin "2") (pinfunction "2_2") (pintype "passive"))
    )
    (net (code "24") (name "Net-(IC3A-OUT)") (class "Default")
      (node (ref "IC3") (pin "1") (pinfunction "OUT_1") (pintype "output"))
      (node (ref "IC3") (pin "6") (pinfunction "-IN_6") (pintype "input"))
      (node (ref "R16") (pin "2") (pinfunction "2_2") (pintype "passive"))
    )
    (net (code "25") (name "Net-(IC3B-+IN)") (class "Default")
      (node (ref "IC3") (pin "5") (pinfunction "+IN_5") (pintype "input"))
      (node (ref "R18") (pin "2") (pinfunction "2_2") (pintype "passive"))
      (node (ref "R19") (pin "1") (pinfunction "1_1") (pintype "passive"))
    )
    (net (code "26") (name "Net-(IC3B-OUT)") (class "Default")
      (node (ref "IC3") (pin "7") (pinfunction "OUT_7") (pintype "output"))
      (node (ref "R19") (pin "2") (pinfunction "2_2") (pintype "passive"))
      (node (ref "R21") (pin "2") (pinfunction "2_2") (pintype "passive"))
    )
    (net (code "27") (name "Net-(IC4A--IN)") (class "Default")
      (node (ref "IC4") (pin "2") (pinfunction "-IN_2") (pintype "input"))
      (node (ref "R13") (pin "2") (pinfunction "2_2") (pintype "passive"))
      (node (ref "R14") (pin "1") (pinfunction "1_1") (pintype "passive"))
      (node (ref "R15") (pin "1") (pinfunction "1_1") (pintype "passive"))
      (node (ref "R17") (pin "2") (pinfunction "2_2") (pintype "passive"))
    )
    (net (code "28") (name "Net-(IC4B--IN)") (class "Default")
      (node (ref "IC4") (pin "6") (pinfunction "-IN_6") (pintype "input"))
      (node (ref "R24") (pin "1") (pinfunction "1_1") (pintype "passive"))
      (node (ref "R25") (pin "2") (pinfunction "2_2") (pintype "passive"))
    )
    (net (code "29") (name "Net-(IC4B-OUT)") (class "Default")
      (node (ref "D4") (pin "A") (pinfunction "A_A") (pintype "passive"))
      (node (ref "IC4") (pin "7") (pinfunction "OUT_7") (pintype "output"))
      (node (ref "R25") (pin "1") (pinfunction "1_1") (pintype "passive"))
      (node (ref "R27") (pin "2") (pinfunction "2_2") (pintype "passive"))
    )
    (net (code "30") (name "Net-(IC5A--IN)") (class "Default")
      (node (ref "C14") (pin "1") (pinfunction "1_1") (pintype "passive"))
      (node (ref "IC5") (pin "2") (pinfunction "-IN_2") (pintype "input"))
      (node (ref "R28") (pin "2") (pinfunction "2_2") (pintype "passive"))
      (node (ref "R30") (pin "2") (pinfunction "2_2") (pintype "passive"))
      (node (ref "R31") (pin "2") (pinfunction "2_2") (pintype "passive"))
      (node (ref "R32") (pin "2") (pinfunction "2_2") (pintype "passive"))
    )
    (net (code "31") (name "Net-(IC5A-OUT)") (class "Default")
      (node (ref "C14") (pin "2") (pinfunction "2_2") (pintype "passive"))
      (node (ref "IC5") (pin "1") (pinfunction "OUT_1") (pintype "output"))
      (node (ref "R32") (pin "1") (pinfunction "1_1") (pintype "passive"))
      (node (ref "R33") (pin "2") (pinfunction "2_2") (pintype "passive"))
    )
    (net (code "32") (name "Net-(IC5B-+IN)") (class "Default")
      (node (ref "IC5") (pin "5") (pinfunction "+IN_5") (pintype "input"))
      (node (ref "R35") (pin "1") (pinfunction "1_1") (pintype "passive"))
      (node (ref "R36") (pin "1") (pinfunction "1_1") (pintype "passive"))
    )
    (net (code "33") (name "Net-(IC5B--IN)") (class "Default")
      (node (ref "IC5") (pin "6") (pinfunction "-IN_6") (pintype "input"))
      (node (ref "R47") (pin "2") (pinfunction "2_2") (pintype "passive"))
    )
    (net (code "34") (name "Net-(IC5B-OUT)") (class "Default")
      (node (ref "IC5") (pin "7") (pinfunction "OUT_7") (pintype "output"))
      (node (ref "R47") (pin "1") (pinfunction "1_1") (pintype "passive"))
      (node (ref "TR4") (pin "1") (pinfunction "1_1") (pintype "passive"))
      (node (ref "TR4") (pin "2") (pinfunction "2_2") (pintype "passive"))
    )
    (net (code "35") (name "Net-(IC6A-+IN)") (class "Default")
      (node (ref "IC6") (pin "3") (pinfunction "+IN_3") (pintype "input"))
      (node (ref "R41") (pin "2") (pinfunction "2_2") (pintype "passive"))
      (node (ref "R43") (pin "1") (pinfunction "1_1") (pintype "passive"))
      (node (ref "TP2") (pin "3") (pinfunction "C_3") (pintype "bidirectional"))
    )
    (net (code "36") (name "Net-(IC6A--IN)") (class "Default")
      (node (ref "C17") (pin "1") (pinfunction "1_1") (pintype "passive"))
      (node (ref "IC6") (pin "2") (pinfunction "-IN_2") (pintype "input"))
      (node (ref "R38") (pin "2") (pinfunction "2_2") (pintype "passive"))
      (node (ref "R44") (pin "2") (pinfunction "2_2") (pintype "passive"))
      (node (ref "TP2") (pin "6") (pinfunction "C_6") (pintype "bidirectional"))
    )
    (net (code "37") (name "Net-(IC6A-OUT)") (class "Default")
      (node (ref "C17") (pin "2") (pinfunction "2_2") (pintype "passive"))
      (node (ref "IC6") (pin "1") (pinfunction "OUT_1") (pintype "output"))
      (node (ref "IC6") (pin "5") (pinfunction "+IN_5") (pintype "input"))
      (node (ref "R44") (pin "1") (pinfunction "1_1") (pintype "passive"))
    )
    (net (code "38") (name "Net-(IC6B--IN)") (class "Default")
      (node (ref "IC6") (pin "6") (pinfunction "-IN_6") (pintype "input"))
      (node (ref "R45") (pin "2") (pinfunction "2_2") (pintype "passive"))
      (node (ref "R46") (pin "2") (pinfunction "2_2") (pintype "passive"))
    )
    (net (code "39") (name "Net-(IC7A--IN)") (class "Default")
      (node (ref "IC7") (pin "2") (pinfunction "-IN_2") (pintype "input"))
      (node (ref "R48") (pin "2") (pinfunction "2_2") (pintype "passive"))
      (node (ref "R49") (pin "2") (pinfunction "2_2") (pintype "passive"))
      (node (ref "R50") (pin "2") (pinfunction "2_2") (pintype "passive"))
      (node (ref "R51") (pin "2") (pinfunction "2_2") (pintype "passive"))
      (node (ref "R52") (pin "1") (pinfunction "1_1") (pintype "passive"))
    )
    (net (code "40") (name "Net-(IC7A-OUT)") (class "Default")
      (node (ref "IC7") (pin "1") (pinfunction "OUT_1") (pintype "output"))
      (node (ref "MIX") (pin "TIP") (pinfunction "TIP_TIP") (pintype "passive"))
      (node (ref "R52") (pin "2") (pinfunction "2_2") (pintype "passive"))
    )
    (net (code "41") (name "Net-(IC7B--IN)") (class "Default")
      (node (ref "IC7") (pin "6") (pinfunction "-IN_6") (pintype "input"))
      (node (ref "IC7") (pin "7") (pinfunction "OUT_7") (pintype "output"))
    )
    (net (code "42") (name "Net-(PULSE_MIX-2)") (class "Default")
      (node (ref "PULSE_MIX") (pin "P$2") (pinfunction "2_P$2") (pintype "passive"))
      (node (ref "R50") (pin "1") (pinfunction "1_1") (pintype "passive"))
    )
    (net (code "43") (name "Net-(PULSE_WIDTH-2)") (class "Default")
      (node (ref "PULSE_WIDTH") (pin "P$2") (pinfunction "2_P$2") (pintype "passive"))
      (node (ref "R9") (pin "1") (pinfunction "1_1") (pintype "passive"))
    )
    (net (code "44") (name "Net-(PWM_LEVEL-2)") (class "Default")
      (node (ref "PWM_LEVEL") (pin "P$2") (pinfunction "2_P$2") (pintype "passive"))
      (node (ref "R10") (pin "1") (pinfunction "1_1") (pintype "passive"))
    )
    (net (code "45") (name "Net-(PWM_LEVEL-3)") (class "Default")
      (node (ref "PWM_IN") (pin "TIP") (pinfunction "TIP_TIP") (pintype "passive"))
      (node (ref "PWM_LEVEL") (pin "P$3") (pinfunction "3_P$3") (pintype "passive"))
    )
    (net (code "46") (name "Net-(R6-Pad2)") (class "Default")
      (node (ref "R6") (pin "2") (pinfunction "2_2") (pintype "passive"))
      (node (ref "TR1") (pin "1") (pinfunction "1_1") (pintype "passive"))
    )
    (net (code "47") (name "Net-(R13-Pad1)") (class "Default")
      (node (ref "R13") (pin "1") (pinfunction "1_1") (pintype "passive"))
      (node (ref "TR2") (pin "2") (pinfunction "2_2") (pintype "passive"))
    )
    (net (code "48") (name "Net-(R30-Pad1)") (class "Default")
      (node (ref "R30") (pin "1") (pinfunction "1_1") (pintype "passive"))
      (node (ref "TR3") (pin "2") (pinfunction "2_2") (pintype "passive"))
    )
    (net (code "49") (name "Net-(R40-Pad1)") (class "Default")
      (node (ref "R40") (pin "1") (pinfunction "1_1") (pintype "passive"))
      (node (ref "TR5") (pin "2") (pinfunction "2_2") (pintype "passive"))
    )
    (net (code "50") (name "Net-(SAW_MIX-2)") (class "Default")
      (node (ref "R48") (pin "1") (pinfunction "1_1") (pintype "passive"))
      (node (ref "SAW_MIX") (pin "P$2") (pinfunction "2_P$2") (pintype "passive"))
    )
    (net (code "51") (name "Net-(SINE_MIX-2)") (class "Default")
      (node (ref "R51") (pin "1") (pinfunction "1_1") (pintype "passive"))
      (node (ref "SINE_MIX") (pin "P$2") (pinfunction "2_P$2") (pintype "passive"))
    )
    (net (code "52") (name "Net-(TP1B-B)") (class "Default")
      (node (ref "TP1") (pin "1") (pinfunction "B_1") (pintype "bidirectional"))
      (node (ref "TR1") (pin "2") (pinfunction "2_2") (pintype "passive"))
    )
    (net (code "53") (name "Net-(TP2A-B)") (class "Default")
      (node (ref "R42") (pin "1") (pinfunction "1_1") (pintype "passive"))
      (node (ref "TP2") (pin "2") (pinfunction "B_2") (pintype "bidirectional"))
    )
    (net (code "54") (name "Net-(TP2A-E)") (class "Default")
      (node (ref "R39") (pin "2") (pinfunction "2_2") (pintype "passive"))
      (node (ref "TP2") (pin "4") (pinfunction "E_4") (pintype "bidirectional"))
      (node (ref "TR5") (pin "3") (pinfunction "3_3") (pintype "passive"))
    )
    (net (code "55") (name "Net-(TP2B-B)") (class "Default")
      (node (ref "R37") (pin "1") (pinfunction "1_1") (pintype "passive"))
      (node (ref "TP2") (pin "1") (pinfunction "B_1") (pintype "bidirectional"))
      (node (ref "TR4") (pin "3") (pinfunction "3_3") (pintype "passive"))
    )
    (net (code "56") (name "Net-(TP2B-E)") (class "Default")
      (node (ref "R39") (pin "1") (pinfunction "1_1") (pintype "passive"))
      (node (ref "TP2") (pin "5") (pinfunction "E_5") (pintype "bidirectional"))
      (node (ref "TR5") (pin "1") (pinfunction "1_1") (pintype "passive"))
    )
    (net (code "57") (name "Net-(TRI_MIX-2)") (class "Default")
      (node (ref "R49") (pin "1") (pinfunction "1_1") (pintype "passive"))
      (node (ref "TRI_MIX") (pin "P$2") (pinfunction "2_P$2") (pintype "passive"))
    )
    (net (code "58") (name "PULSE") (class "Default")
      (node (ref "PULSE") (pin "TIP") (pinfunction "TIP_TIP") (pintype "passive"))
      (node (ref "PULSE_MIX") (pin "P$3") (pinfunction "3_P$3") (pintype "passive"))
      (node (ref "R21") (pin "1") (pinfunction "1_1") (pintype "passive"))
      (node (ref "R22") (pin "2") (pinfunction "2_2") (pintype "passive"))
    )
    (net (code "59") (name "PULSEIN") (class "Default")
      (node (ref "C13") (pin "1") (pinfunction "1_1") (pintype "passive"))
      (node (ref "D3") (pin "A") (pinfunction "A_A") (pintype "passive"))
      (node (ref "IC4") (pin "1") (pinfunction "OUT_1") (pintype "output"))
      (node (ref "R17") (pin "1") (pinfunction "1_1") (pintype "passive"))
      (node (ref "R18") (pin "1") (pinfunction "1_1") (pintype "passive"))
      (node (ref "R24") (pin "2") (pinfunction "2_2") (pintype "passive"))
    )
    (net (code "60") (name "SAW") (class "Default")
      (node (ref "R27") (pin "1") (pinfunction "1_1") (pintype "passive"))
      (node (ref "R29") (pin "1") (pinfunction "1_1") (pintype "passive"))
      (node (ref "SAW") (pin "TIP") (pinfunction "TIP_TIP") (pintype "passive"))
      (node (ref "SAW_MIX") (pin "P$3") (pinfunction "3_P$3") (pintype "passive"))
    )
    (net (code "61") (name "SAWCORE") (class "Default")
      (node (ref "IC2") (pin "1") (pinfunction "OUT_1") (pintype "output"))
      (node (ref "R11") (pin "1") (pinfunction "1_1") (pintype "passive"))
      (node (ref "R12") (pin "1") (pinfunction "1_1") (pintype "passive"))
      (node (ref "R14") (pin "2") (pinfunction "2_2") (pintype "passive"))
    )
    (net (code "62") (name "SINE") (class "Default")
      (node (ref "IC6") (pin "7") (pinfunction "OUT_7") (pintype "output"))
      (node (ref "R46") (pin "1") (pinfunction "1_1") (pintype "passive"))
      (node (ref "SINE") (pin "TIP") (pinfunction "TIP_TIP") (pintype "passive"))
      (node (ref "SINE_MIX") (pin "P$3") (pinfunction "3_P$3") (pintype "passive"))
    )
    (net (code "63") (name "TRI") (class "Default")
      (node (ref "R33") (pin "1") (pinfunction "1_1") (pintype "passive"))
      (node (ref "R34") (pin "1") (pinfunction "1_1") (pintype "passive"))
      (node (ref "R35") (pin "2") (pinfunction "2_2") (pintype "passive"))
      (node (ref "TRI") (pin "TIP") (pinfunction "TIP_TIP") (pintype "passive"))
      (node (ref "TRI_MIX") (pin "P$3") (pinfunction "3_P$3") (pintype "passive"))
    )
    (net (code "64") (name "unconnected-(IC8-NC-Pad3)") (class "Default")
      (node (ref "IC8") (pin "3") (pinfunction "NC_3") (pintype "no_connect"))
    )
    (net (code "65") (name "unconnected-(MIX-SWITCH-PadNORM)") (class "Default")
      (node (ref "MIX") (pin "NORM") (pinfunction "SWITCH_NORM") (pintype "passive"))
    )
    (net (code "66") (name "unconnected-(PULSE-SWITCH-PadNORM)") (class "Default")
      (node (ref "PULSE") (pin "NORM") (pinfunction "SWITCH_NORM") (pintype "passive"))
    )
    (net (code "67") (name "unconnected-(PWM_IN-SWITCH-PadNORM)") (class "Default")
      (node (ref "PWM_IN") (pin "NORM") (pinfunction "SWITCH_NORM") (pintype "passive"))
    )
    (net (code "68") (name "unconnected-(SAW-SWITCH-PadNORM)") (class "Default")
      (node (ref "SAW") (pin "NORM") (pinfunction "SWITCH_NORM") (pintype "passive"))
    )
    (net (code "69") (name "unconnected-(SINE-SWITCH-PadNORM)") (class "Default")
      (node (ref "SINE") (pin "NORM") (pinfunction "SWITCH_NORM") (pintype "passive"))
    )
    (net (code "70") (name "unconnected-(SYNC-SWITCH-PadNORM)") (class "Default")
      (node (ref "SYNC") (pin "NORM") (pinfunction "SWITCH_NORM") (pintype "passive"))
    )
    (net (code "71") (name "unconnected-(TRI-SWITCH-PadNORM)") (class "Default")
      (node (ref "TRI") (pin "NORM") (pinfunction "SWITCH_NORM") (pintype "passive"))
    )
  )
)
